# 800U_R3N3_SONSER_V1_0.net
KiCad netlist of a schematic drawn in Altium Designer
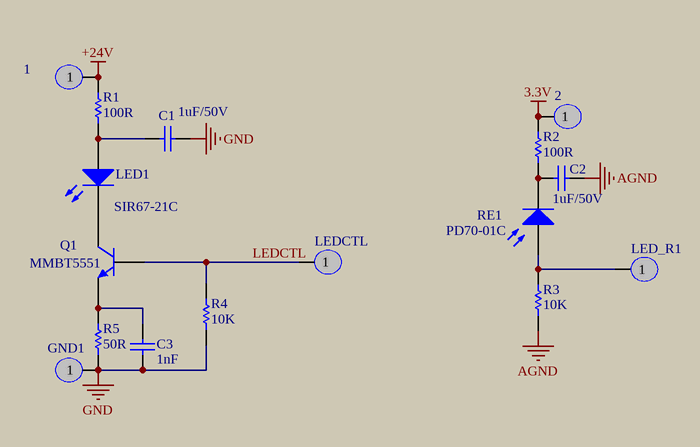
[diagram p0: 800U R3N3_SONSER_V1.0.SchDoc]

(export (version "E")
  (design (tool "Eeschema 10.0.6"))
  (components
    (comp (ref "1") (value "~") (footprint "HOLE_SMD") (libsource (lib "MODBUS_V1.0") (part "焊盘")))
    (comp (ref "2") (value "~") (footprint "HOLE_SMD") (libsource (lib "") (part "焊盘_1")))
    (comp (ref "C1")
      (value "1uF/50V")
      (footprint "C0805")
      (description "贴片电容")
      (fields (field (name "Comment") "105") (field (name "PUBLISHER") "Altium Limited"))
      (libsource (lib "TMJD1.0") (part "Cap"))
    )
    (comp (ref "C2")
      (value "1uF/50V")
      (footprint "C0603")
      (description "贴片电容")
      (fields (field (name "Comment") "105") (field (name "PUBLISHER") "Altium Limited"))
      (libsource (lib "TMJD1.0") (part "Cap"))
    )
    (comp (ref "C3")
      (value "1nF")
      (footprint "C0603")
      (description "贴片电容")
      (fields (field (name "Comment") "102") (field (name "PUBLISHER") "Altium Limited"))
      (libsource (lib "TMJD1.0") (part "Cap"))
    )
    (comp (ref "GND1") (value "~") (footprint "HOLE_SMD") (libsource (lib "MODBUS_V1.0") (part "焊盘")))
    (comp (ref "LED1")
      (value "SIR67-21C")
      (footprint "LED-3.5X2.8")
      (description "贴片红外发射管")
      (fields (field (name "PUBLISHER") "Altium Limited"))
      (libsource (lib "Miscellaneous Devices") (part "LED0"))
    )
    (comp (ref "LEDCTL") (value "~") (footprint "HOLE_SMD") (libsource (lib "MODBUS_V1.0") (part "焊盘")))
    (comp (ref "LED_R1") (value "~") (footprint "HOLE_SMD") (libsource (lib "") (part "焊盘_1")))
    (comp (ref "Q1")
      (value "MMBT5551")
      (footprint "SOT-23")
      (description "贴片NPN三极管")
      (libsource (lib "Miscellaneous Devices") (part "NPN"))
    )
    (comp (ref "R1")
      (value "100R")
      (footprint "R0805")
      (description "贴片电阻")
      (fields (field (name "Comment") "100"))
      (libsource (lib "Miscellaneous Devices") (part "Res Semi"))
    )
    (comp (ref "R2")
      (value "100R")
      (footprint "R0805")
      (description "贴片电阻")
      (fields (field (name "Comment") "100"))
      (libsource (lib "Miscellaneous Devices") (part "Res Semi"))
    )
    (comp (ref "R3")
      (value "10K")
      (footprint "R0603")
      (description "贴片电阻")
      (libsource (lib "Miscellaneous Devices") (part "Res Semi"))
    )
    (comp (ref "R4")
      (value "10K")
      (footprint "R0603")
      (description "贴片电阻")
      (libsource (lib "Miscellaneous Devices") (part "Res Semi"))
    )
    (comp (ref "R5")
      (value "50R")
      (footprint "R0805")
      (description "贴片电阻")
      (fields (field (name "Comment") "15"))
      (libsource (lib "Miscellaneous Devices") (part "Res Semi"))
    )
    (comp (ref "RE1")
      (value "PD70-01C")
      (footprint "LED9*4")
      (description "贴片接收管")
      (fields (field (name "PUBLISHER") "Altium Limited"))
      (libsource (lib "Miscellaneous Devices") (part "Photo Sen"))
    )
  )
  (nets
    (net (code "1") (name "+24V") (class "Default")
      (node (ref "1") (pin "1") (pinfunction "1_1") (pintype "passive"))
      (node (ref "R1") (pin "2") (pinfunction "2_2") (pintype "passive"))
    )
    (net (code "2") (name "/LEDCTL") (class "Default")
      (node (ref "LEDCTL") (pin "1") (pinfunction "1_1") (pintype "passive"))
      (node (ref "Q1") (pin "1") (pinfunction "B_1") (pintype "passive"))
      (node (ref "R4") (pin "2") (pinfunction "2_2") (pintype "passive"))
    )
    (net (code "3") (name "3.3V") (class "Default")
      (node (ref "2") (pin "1") (pinfunction "1_1") (pintype "passive"))
      (node (ref "R2") (pin "2") (pinfunction "2_2") (pintype "passive"))
    )
    (net (code "4") (name "AGND") (class "Default")
      (node (ref "C2") (pin "2") (pinfunction "2_2") (pintype "passive"))
      (node (ref "R3") (pin "1") (pinfunction "1_1") (pintype "passive"))
    )
    (net (code "5") (name "GND") (class "Default")
      (node (ref "C1") (pin "2") (pinfunction "2_2") (pintype "passive"))
      (node (ref "C3") (pin "2") (pinfunction "2_2") (pintype "passive"))
      (node (ref "GND1") (pin "1") (pinfunction "1_1") (pintype "passive"))
      (node (ref "R4") (pin "1") (pinfunction "1_1") (pintype "passive"))
      (node (ref "R5") (pin "1") (pinfunction "1_1") (pintype "passive"))
    )
    (net (code "6") (name "Net-(LED1-A)") (class "Default")
      (node (ref "C1") (pin "1") (pinfunction "1_1") (pintype "passive"))
      (node (ref "LED1") (pin "1") (pinfunction "A_1") (pintype "passive"))
      (node (ref "R1") (pin "1") (pinfunction "1_1") (pintype "passive"))
    )
    (net (code "7") (name "Net-(LED1-K)") (class "Default")
      (node (ref "LED1") (pin "2") (pinfunction "K_2") (pintype "passive"))
      (node (ref "Q1") (pin "3") (pinfunction "C_3") (pintype "passive"))
    )
    (net (code "8") (name "Net-(Q1-E)") (class "Default")
      (node (ref "C3") (pin "1") (pinfunction "1_1") (pintype "passive"))
      (node (ref "Q1") (pin "2") (pinfunction "E_2") (pintype "passive"))
      (node (ref "R5") (pin "2") (pinfunction "2_2") (pintype "passive"))
    )
    (net (code "9") (name "Net-(RE1-A)") (class "Default")
      (node (ref "LED_R1") (pin "1") (pinfunction "1_1") (pintype "passive"))
      (node (ref "R3") (pin "2") (pinfunction "2_2") (pintype "passive"))
      (node (ref "RE1") (pin "1") (pinfunction "A_1") (pintype "passive"))
    )
    (net (code "10") (name "Net-(RE1-K)") (class "Default")
      (node (ref "C2") (pin "1") (pinfunction "1_1") (pintype "passive"))
      (node (ref "R2") (pin "1") (pinfunction "1_1") (pintype "passive"))
      (node (ref "RE1") (pin "2") (pinfunction "K_2") (pintype "passive"))
    )
  )
)
